# Schematic-sensor.net
KiCad netlist of a schematic drawn in Altium Designer
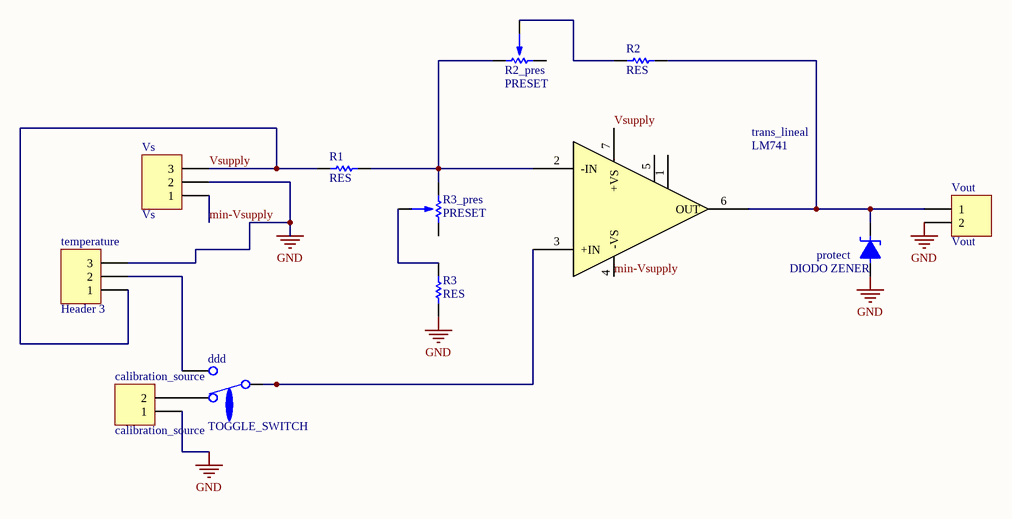
[diagram p0: Schematic-sensor.SchDoc]

(export (version "E")
  (design (tool "Eeschema 10.0.6"))
  (components
    (comp (ref "calibration_source")
      (value "calibration_source")
      (footprint "HDR1X2")
      (description "Header, 2-Pin")
      (fields (field (name "PUBLISHER") "Altium Limited"))
      (libsource (lib "Miscellaneous Connectors") (part "Header 2"))
    )
    (comp (ref "ddd")
      (value "TOGGLE_SWITCH")
      (footprint "TOOGLE SWITCH SIMPLE")
      (description "Pulsador con reteción")
      (libsource (lib "LIBEBAL") (part "TOGGLE_SWITCH"))
    )
    (comp (ref "protect")
      (value "DIODO ZENER")
      (footprint "DO41")
      (libsource (lib "LIBEBAL") (part "DIODO ZENER"))
    )
    (comp (ref "R1") (value "RES") (footprint "RES400") (libsource (lib "LIBEBAL") (part "RES")))
    (comp (ref "R2") (value "RES") (footprint "RES400") (libsource (lib "LIBEBAL") (part "RES")))
    (comp (ref "R2_pres") (value "PRESET") (footprint "PRESET V") (libsource (lib "LIBEBAL") (part "PRESET")))
    (comp (ref "R3") (value "RES") (footprint "RES400") (libsource (lib "LIBEBAL") (part "RES")))
    (comp (ref "R3_pres") (value "PRESET") (footprint "PRESET V") (libsource (lib "LIBEBAL") (part "PRESET")))
    (comp (ref "temperature")
      (value "Header 3")
      (footprint "HDR1X3")
      (description "Header, 3-Pin")
      (fields (field (name "PUBLISHER") "Altium Limited"))
      (libsource (lib "Miscellaneous Connectors") (part "Header 3"))
    )
    (comp (ref "trans_lineal")
      (value "LM741")
      (footprint "DIP8")
      (description "LM741 Operational Amplifier")
      (libsource (lib "LIBEBAL") (part "LM741"))
    )
    (comp (ref "Vout")
      (value "Vout")
      (footprint "HDR1X2")
      (description "Header, 2-Pin")
      (fields (field (name "PUBLISHER") "Altium Limited"))
      (libsource (lib "") (part "Header 2_1"))
    )
    (comp (ref "Vs")
      (value "Vs")
      (footprint "HDR1X3")
      (description "Header, 3-Pin")
      (fields (field (name "PUBLISHER") "Altium Limited"))
      (libsource (lib "Miscellaneous Connectors") (part "Header 3"))
    )
  )
  (nets
    (net (code "1") (name "/Vsupply") (class "Default")
      (node (ref "R1") (pin "1") (pinfunction "1_1") (pintype "passive"))
      (node (ref "Vs") (pin "3") (pinfunction "3_3") (pintype "passive"))
      (node (ref "temperature") (pin "1") (pinfunction "1_1") (pintype "passive"))
      (node (ref "trans_lineal") (pin "7") (pinfunction "+VS_7") (pintype "passive"))
    )
    (net (code "2") (name "/min-Vsupply") (class "Default")
      (node (ref "Vs") (pin "1") (pinfunction "1_1") (pintype "passive"))
      (node (ref "trans_lineal") (pin "4") (pinfunction "-VS_4") (pintype "passive"))
    )
    (net (code "3") (name "GND") (class "Default")
      (node (ref "R3") (pin "1") (pinfunction "1_1") (pintype "passive"))
      (node (ref "Vout") (pin "2") (pinfunction "2_2") (pintype "passive"))
      (node (ref "Vs") (pin "2") (pinfunction "2_2") (pintype "passive"))
      (node (ref "calibration_source") (pin "1") (pinfunction "1_1") (pintype "passive"))
      (node (ref "protect") (pin "1") (pinfunction "1_1") (pintype "passive"))
      (node (ref "temperature") (pin "3") (pinfunction "3_3") (pintype "passive"))
    )
    (net (code "4") (name "Net-(R2-Pad1)") (class "Default")
      (node (ref "R2") (pin "1") (pinfunction "1_1") (pintype "passive"))
      (node (ref "R2_pres") (pin "2") (pinfunction "2_2") (pintype "passive"))
    )
    (net (code "5") (name "Net-(R3-Pad2)") (class "Default")
      (node (ref "R3") (pin "2") (pinfunction "2_2") (pintype "passive"))
      (node (ref "R3_pres") (pin "2") (pinfunction "2_2") (pintype "passive"))
    )
    (net (code "6") (name "Net-(ddd-C)") (class "Default")
      (node (ref "ddd") (pin "2") (pinfunction "C_2") (pintype "passive"))
      (node (ref "trans_lineal") (pin "3") (pinfunction "+IN_3") (pintype "passive"))
    )
    (net (code "7") (name "Net-(ddd-NA)") (class "Default")
      (node (ref "ddd") (pin "1") (pinfunction "NA_1") (pintype "passive"))
      (node (ref "temperature") (pin "2") (pinfunction "2_2") (pintype "passive"))
    )
    (net (code "8") (name "Net-(ddd-NC)") (class "Default")
      (node (ref "calibration_source") (pin "2") (pinfunction "2_2") (pintype "passive"))
      (node (ref "ddd") (pin "3") (pinfunction "NC_3") (pintype "passive"))
    )
    (net (code "9") (name "Net-(trans_lineal--IN)") (class "Default")
      (node (ref "R1") (pin "2") (pinfunction "2_2") (pintype "passive"))
      (node (ref "R2_pres") (pin "1") (pinfunction "1_1") (pintype "passive"))
      (node (ref "R3_pres") (pin "3") (pinfunction "3_3") (pintype "passive"))
      (node (ref "trans_lineal") (pin "2") (pinfunction "-IN_2") (pintype "passive"))
    )
    (net (code "10") (name "Net-(trans_lineal-OUT)") (class "Default")
      (node (ref "R2") (pin "2") (pinfunction "2_2") (pintype "passive"))
      (node (ref "Vout") (pin "1") (pinfunction "1_1") (pintype "passive"))
      (node (ref "protect") (pin "2") (pinfunction "2_2") (pintype "passive"))
      (node (ref "trans_lineal") (pin "6") (pinfunction "OUT_6") (pintype "passive"))
    )
    (net (code "11") (name "unconnected-(R2_pres-Pad3)") (class "Default")
      (node (ref "R2_pres") (pin "3") (pinfunction "3_3") (pintype "passive"))
    )
    (net (code "12") (name "unconnected-(R3_pres-Pad1)") (class "Default")
      (node (ref "R3_pres") (pin "1") (pinfunction "1_1") (pintype "passive"))
    )
    (net (code "13") (name "unconnected-(trans_lineal-+RG-Pad5)") (class "Default")
      (node (ref "trans_lineal") (pin "5") (pinfunction "+RG_5") (pintype "passive"))
    )
    (net (code "14") (name "unconnected-(trans_lineal--RG-Pad1)") (class "Default")
      (node (ref "trans_lineal") (pin "1") (pinfunction "-RG_1") (pintype "passive"))
    )
  )
)
